# Sheet4.net
KiCad netlist of a schematic drawn in Altium Designer
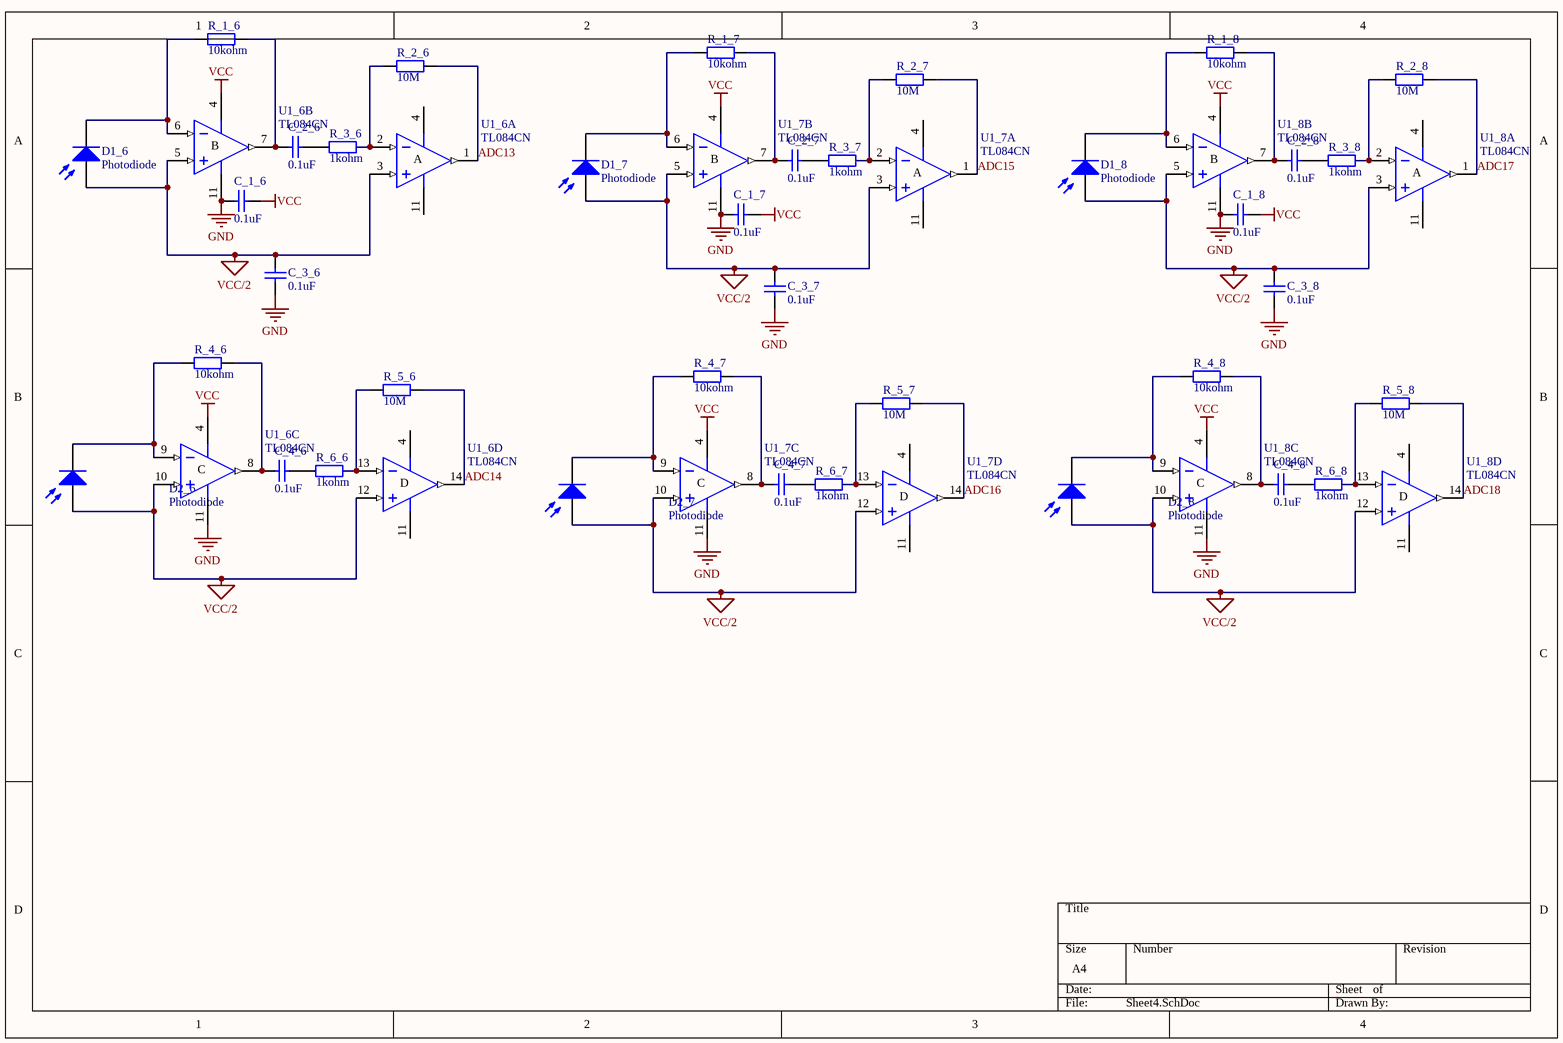
[diagram p0: Sheet4.SchDoc]

(export (version "E")
  (design (tool "Eeschema 10.0.6"))
  (components
    (comp (ref "C_1_6")
      (value "0.1uF")
      (footprint "cms805 - mini")
      (libsource (lib "lib_Robotronik") (part "Capa"))
    )
    (comp (ref "C_1_7")
      (value "0.1uF")
      (footprint "cms805 - mini")
      (libsource (lib "lib_Robotronik") (part "Capa"))
    )
    (comp (ref "C_1_8")
      (value "0.1uF")
      (footprint "cms805 - mini")
      (libsource (lib "lib_Robotronik") (part "Capa"))
    )
    (comp (ref "C_2_6")
      (value "0.1uF")
      (footprint "cms805 - mini")
      (libsource (lib "lib_Robotronik") (part "Capa"))
    )
    (comp (ref "C_2_7")
      (value "0.1uF")
      (footprint "cms805 - mini")
      (libsource (lib "lib_Robotronik") (part "Capa"))
    )
    (comp (ref "C_2_8")
      (value "0.1uF")
      (footprint "cms805 - mini")
      (libsource (lib "lib_Robotronik") (part "Capa"))
    )
    (comp (ref "C_3_6")
      (value "0.1uF")
      (footprint "cms805 - mini")
      (libsource (lib "lib_Robotronik") (part "Capa"))
    )
    (comp (ref "C_3_7")
      (value "0.1uF")
      (footprint "cms805 - mini")
      (libsource (lib "lib_Robotronik") (part "Capa"))
    )
    (comp (ref "C_3_8")
      (value "0.1uF")
      (footprint "cms805 - mini")
      (libsource (lib "lib_Robotronik") (part "Capa"))
    )
    (comp (ref "C_4_6")
      (value "0.1uF")
      (footprint "cms805 - mini")
      (libsource (lib "lib_Robotronik") (part "Capa"))
    )
    (comp (ref "C_4_7")
      (value "0.1uF")
      (footprint "cms805 - mini")
      (libsource (lib "lib_Robotronik") (part "Capa"))
    )
    (comp (ref "C_4_8")
      (value "0.1uF")
      (footprint "cms805 - mini")
      (libsource (lib "lib_Robotronik") (part "Capa"))
    )
    (comp (ref "D1_6")
      (value "Photodiode")
      (footprint "TEMD1000")
      (fields (field (name "PUBLISHER") "Altium Limited"))
      (libsource (lib "lib_Robotronik") (part "Photodiode"))
    )
    (comp (ref "D1_7")
      (value "Photodiode")
      (footprint "TEMD1000")
      (fields (field (name "PUBLISHER") "Altium Limited"))
      (libsource (lib "lib_Robotronik") (part "Photodiode"))
    )
    (comp (ref "D1_8")
      (value "Photodiode")
      (footprint "TEMD1000")
      (fields (field (name "PUBLISHER") "Altium Limited"))
      (libsource (lib "lib_Robotronik") (part "Photodiode"))
    )
    (comp (ref "D2_6")
      (value "Photodiode")
      (footprint "TEMD1000")
      (fields (field (name "PUBLISHER") "Altium Limited"))
      (libsource (lib "lib_Robotronik") (part "Photodiode"))
    )
    (comp (ref "D2_7")
      (value "Photodiode")
      (footprint "TEMD1000")
      (fields (field (name "PUBLISHER") "Altium Limited"))
      (libsource (lib "lib_Robotronik") (part "Photodiode"))
    )
    (comp (ref "D2_8")
      (value "Photodiode")
      (footprint "TEMD1000")
      (fields (field (name "PUBLISHER") "Altium Limited"))
      (libsource (lib "lib_Robotronik") (part "Photodiode"))
    )
    (comp (ref "R_1_6")
      (value "10kohm")
      (footprint "cms805 - mini")
      (libsource (lib "lib_Robotronik") (part "Resistance"))
    )
    (comp (ref "R_1_7")
      (value "10kohm")
      (footprint "cms805 - mini")
      (libsource (lib "lib_Robotronik") (part "Resistance"))
    )
    (comp (ref "R_1_8")
      (value "10kohm")
      (footprint "cms805 - mini")
      (libsource (lib "lib_Robotronik") (part "Resistance"))
    )
    (comp (ref "R_2_6")
      (value "10M")
      (footprint "cms805 - mini")
      (libsource (lib "lib_Robotronik") (part "Resistance"))
    )
    (comp (ref "R_2_7")
      (value "10M")
      (footprint "cms805 - mini")
      (libsource (lib "lib_Robotronik") (part "Resistance"))
    )
    (comp (ref "R_2_8")
      (value "10M")
      (footprint "cms805 - mini")
      (libsource (lib "lib_Robotronik") (part "Resistance"))
    )
    (comp (ref "R_3_6")
      (value "1kohm")
      (footprint "cms805 - mini")
      (libsource (lib "lib_Robotronik") (part "Resistance"))
    )
    (comp (ref "R_3_7")
      (value "1kohm")
      (footprint "cms805 - mini")
      (libsource (lib "lib_Robotronik") (part "Resistance"))
    )
    (comp (ref "R_3_8")
      (value "1kohm")
      (footprint "cms805 - mini")
      (libsource (lib "lib_Robotronik") (part "Resistance"))
    )
    (comp (ref "R_4_6")
      (value "10kohm")
      (footprint "cms805 - mini")
      (libsource (lib "lib_Robotronik") (part "Resistance"))
    )
    (comp (ref "R_4_7")
      (value "10kohm")
      (footprint "cms805 - mini")
      (libsource (lib "lib_Robotronik") (part "Resistance"))
    )
    (comp (ref "R_4_8")
      (value "10kohm")
      (footprint "cms805 - mini")
      (libsource (lib "lib_Robotronik") (part "Resistance"))
    )
    (comp (ref "R_5_6")
      (value "10M")
      (footprint "cms805 - mini")
      (libsource (lib "lib_Robotronik") (part "Resistance"))
    )
    (comp (ref "R_5_7")
      (value "10M")
      (footprint "cms805 - mini")
      (libsource (lib "lib_Robotronik") (part "Resistance"))
    )
    (comp (ref "R_5_8")
      (value "10M")
      (footprint "cms805 - mini")
      (libsource (lib "lib_Robotronik") (part "Resistance"))
    )
    (comp (ref "R_6_6")
      (value "1kohm")
      (footprint "cms805 - mini")
      (libsource (lib "lib_Robotronik") (part "Resistance"))
    )
    (comp (ref "R_6_7")
      (value "1kohm")
      (footprint "cms805 - mini")
      (libsource (lib "lib_Robotronik") (part "Resistance"))
    )
    (comp (ref "R_6_8")
      (value "1kohm")
      (footprint "cms805 - mini")
      (libsource (lib "lib_Robotronik") (part "Resistance"))
    )
    (comp (ref "U1_6")
      (value "TL084CN")
      (footprint "TSSOP14")
      (description "General-Purpose J-FET Quad Operational Amplifier")
      (fields (field (name "PUBLISHER") "Altium Limited"))
      (libsource (lib "lib_Robotronik") (part "TL084CN"))
    )
    (comp (ref "U1_7")
      (value "TL084CN")
      (footprint "TSSOP14")
      (description "General-Purpose J-FET Quad Operational Amplifier")
      (fields (field (name "PUBLISHER") "Altium Limited"))
      (libsource (lib "lib_Robotronik") (part "TL084CN"))
    )
    (comp (ref "U1_8")
      (value "TL084CN")
      (footprint "TSSOP14")
      (description "General-Purpose J-FET Quad Operational Amplifier")
      (fields (field (name "PUBLISHER") "Altium Limited"))
      (libsource (lib "lib_Robotronik") (part "TL084CN"))
    )
  )
  (nets
    (net (code "1") (name "/ADC13") (class "Default")
      (node (ref "R_2_6") (pin "2") (pinfunction "2_2") (pintype "passive"))
      (node (ref "U1_6") (pin "1") (pinfunction "OUT_1") (pintype "output"))
    )
    (net (code "2") (name "/ADC14") (class "Default")
      (node (ref "R_5_6") (pin "2") (pinfunction "2_2") (pintype "passive"))
      (node (ref "U1_6") (pin "14") (pinfunction "OUT_14") (pintype "output"))
    )
    (net (code "3") (name "/ADC15") (class "Default")
      (node (ref "R_2_7") (pin "2") (pinfunction "2_2") (pintype "passive"))
      (node (ref "U1_7") (pin "1") (pinfunction "OUT_1") (pintype "output"))
    )
    (net (code "4") (name "/ADC16") (class "Default")
      (node (ref "R_5_7") (pin "2") (pinfunction "2_2") (pintype "passive"))
      (node (ref "U1_7") (pin "14") (pinfunction "OUT_14") (pintype "output"))
    )
    (net (code "5") (name "/ADC17") (class "Default")
      (node (ref "R_2_8") (pin "2") (pinfunction "2_2") (pintype "passive"))
      (node (ref "U1_8") (pin "1") (pinfunction "OUT_1") (pintype "output"))
    )
    (net (code "6") (name "/ADC18") (class "Default")
      (node (ref "R_5_8") (pin "2") (pinfunction "2_2") (pintype "passive"))
      (node (ref "U1_8") (pin "14") (pinfunction "OUT_14") (pintype "output"))
    )
    (net (code "7") (name "GND") (class "Default")
      (node (ref "C_1_6") (pin "1") (pinfunction "1_1") (pintype "passive"))
      (node (ref "C_1_7") (pin "1") (pinfunction "1_1") (pintype "passive"))
      (node (ref "C_1_8") (pin "1") (pinfunction "1_1") (pintype "passive"))
      (node (ref "C_3_6") (pin "1") (pinfunction "1_1") (pintype "passive"))
      (node (ref "C_3_7") (pin "1") (pinfunction "1_1") (pintype "passive"))
      (node (ref "C_3_8") (pin "1") (pinfunction "1_1") (pintype "passive"))
      (node (ref "U1_6") (pin "11") (pinfunction "V-_11") (pintype "power_in"))
      (node (ref "U1_7") (pin "11") (pinfunction "V-_11") (pintype "power_in"))
      (node (ref "U1_8") (pin "11") (pinfunction "V-_11") (pintype "power_in"))
    )
    (net (code "8") (name "Net-(C_2_6-Pad1)") (class "Default")
      (node (ref "C_2_6") (pin "1") (pinfunction "1_1") (pintype "passive"))
      (node (ref "R_3_6") (pin "1") (pinfunction "1_1") (pintype "passive"))
    )
    (net (code "9") (name "Net-(C_2_7-Pad1)") (class "Default")
      (node (ref "C_2_7") (pin "1") (pinfunction "1_1") (pintype "passive"))
      (node (ref "R_3_7") (pin "1") (pinfunction "1_1") (pintype "passive"))
    )
    (net (code "10") (name "Net-(C_2_8-Pad1)") (class "Default")
      (node (ref "C_2_8") (pin "1") (pinfunction "1_1") (pintype "passive"))
      (node (ref "R_3_8") (pin "1") (pinfunction "1_1") (pintype "passive"))
    )
    (net (code "11") (name "Net-(C_4_6-Pad1)") (class "Default")
      (node (ref "C_4_6") (pin "1") (pinfunction "1_1") (pintype "passive"))
      (node (ref "R_6_6") (pin "1") (pinfunction "1_1") (pintype "passive"))
    )
    (net (code "12") (name "Net-(C_4_7-Pad1)") (class "Default")
      (node (ref "C_4_7") (pin "1") (pinfunction "1_1") (pintype "passive"))
      (node (ref "R_6_7") (pin "1") (pinfunction "1_1") (pintype "passive"))
    )
    (net (code "13") (name "Net-(C_4_8-Pad1)") (class "Default")
      (node (ref "C_4_8") (pin "1") (pinfunction "1_1") (pintype "passive"))
      (node (ref "R_6_8") (pin "1") (pinfunction "1_1") (pintype "passive"))
    )
    (net (code "14") (name "Net-(D1_6-K)") (class "Default")
      (node (ref "D1_6") (pin "2") (pinfunction "K_2") (pintype "passive"))
      (node (ref "R_1_6") (pin "1") (pinfunction "1_1") (pintype "passive"))
      (node (ref "U1_6") (pin "6") (pinfunction "IN-_6") (pintype "input"))
    )
    (net (code "15") (name "Net-(D1_7-K)") (class "Default")
      (node (ref "D1_7") (pin "2") (pinfunction "K_2") (pintype "passive"))
      (node (ref "R_1_7") (pin "1") (pinfunction "1_1") (pintype "passive"))
      (node (ref "U1_7") (pin "6") (pinfunction "IN-_6") (pintype "input"))
    )
    (net (code "16") (name "Net-(D1_8-K)") (class "Default")
      (node (ref "D1_8") (pin "2") (pinfunction "K_2") (pintype "passive"))
      (node (ref "R_1_8") (pin "1") (pinfunction "1_1") (pintype "passive"))
      (node (ref "U1_8") (pin "6") (pinfunction "IN-_6") (pintype "input"))
    )
    (net (code "17") (name "Net-(D2_6-K)") (class "Default")
      (node (ref "D2_6") (pin "2") (pinfunction "K_2") (pintype "passive"))
      (node (ref "R_4_6") (pin "1") (pinfunction "1_1") (pintype "passive"))
      (node (ref "U1_6") (pin "9") (pinfunction "IN-_9") (pintype "input"))
    )
    (net (code "18") (name "Net-(D2_7-K)") (class "Default")
      (node (ref "D2_7") (pin "2") (pinfunction "K_2") (pintype "passive"))
      (node (ref "R_4_7") (pin "1") (pinfunction "1_1") (pintype "passive"))
      (node (ref "U1_7") (pin "9") (pinfunction "IN-_9") (pintype "input"))
    )
    (net (code "19") (name "Net-(D2_8-K)") (class "Default")
      (node (ref "D2_8") (pin "2") (pinfunction "K_2") (pintype "passive"))
      (node (ref "R_4_8") (pin "1") (pinfunction "1_1") (pintype "passive"))
      (node (ref "U1_8") (pin "9") (pinfunction "IN-_9") (pintype "input"))
    )
    (net (code "20") (name "Net-(U1_6A-IN-)") (class "Default")
      (node (ref "R_2_6") (pin "1") (pinfunction "1_1") (pintype "passive"))
      (node (ref "R_3_6") (pin "2") (pinfunction "2_2") (pintype "passive"))
      (node (ref "U1_6") (pin "2") (pinfunction "IN-_2") (pintype "input"))
    )
    (net (code "21") (name "Net-(U1_6B-OUT)") (class "Default")
      (node (ref "C_2_6") (pin "2") (pinfunction "2_2") (pintype "passive"))
      (node (ref "R_1_6") (pin "2") (pinfunction "2_2") (pintype "passive"))
      (node (ref "U1_6") (pin "7") (pinfunction "OUT_7") (pintype "output"))
    )
    (net (code "22") (name "Net-(U1_6C-OUT)") (class "Default")
      (node (ref "C_4_6") (pin "2") (pinfunction "2_2") (pintype "passive"))
      (node (ref "R_4_6") (pin "2") (pinfunction "2_2") (pintype "passive"))
      (node (ref "U1_6") (pin "8") (pinfunction "OUT_8") (pintype "output"))
    )
    (net (code "23") (name "Net-(U1_6D-IN-)") (class "Default")
      (node (ref "R_5_6") (pin "1") (pinfunction "1_1") (pintype "passive"))
      (node (ref "R_6_6") (pin "2") (pinfunction "2_2") (pintype "passive"))
      (node (ref "U1_6") (pin "13") (pinfunction "IN-_13") (pintype "input"))
    )
    (net (code "24") (name "Net-(U1_7A-IN-)") (class "Default")
      (node (ref "R_2_7") (pin "1") (pinfunction "1_1") (pintype "passive"))
      (node (ref "R_3_7") (pin "2") (pinfunction "2_2") (pintype "passive"))
      (node (ref "U1_7") (pin "2") (pinfunction "IN-_2") (pintype "input"))
    )
    (net (code "25") (name "Net-(U1_7B-OUT)") (class "Default")
      (node (ref "C_2_7") (pin "2") (pinfunction "2_2") (pintype "passive"))
      (node (ref "R_1_7") (pin "2") (pinfunction "2_2") (pintype "passive"))
      (node (ref "U1_7") (pin "7") (pinfunction "OUT_7") (pintype "output"))
    )
    (net (code "26") (name "Net-(U1_7C-OUT)") (class "Default")
      (node (ref "C_4_7") (pin "2") (pinfunction "2_2") (pintype "passive"))
      (node (ref "R_4_7") (pin "2") (pinfunction "2_2") (pintype "passive"))
      (node (ref "U1_7") (pin "8") (pinfunction "OUT_8") (pintype "output"))
    )
    (net (code "27") (name "Net-(U1_7D-IN-)") (class "Default")
      (node (ref "R_5_7") (pin "1") (pinfunction "1_1") (pintype "passive"))
      (node (ref "R_6_7") (pin "2") (pinfunction "2_2") (pintype "passive"))
      (node (ref "U1_7") (pin "13") (pinfunction "IN-_13") (pintype "input"))
    )
    (net (code "28") (name "Net-(U1_8A-IN-)") (class "Default")
      (node (ref "R_2_8") (pin "1") (pinfunction "1_1") (pintype "passive"))
      (node (ref "R_3_8") (pin "2") (pinfunction "2_2") (pintype "passive"))
      (node (ref "U1_8") (pin "2") (pinfunction "IN-_2") (pintype "input"))
    )
    (net (code "29") (name "Net-(U1_8B-OUT)") (class "Default")
      (node (ref "C_2_8") (pin "2") (pinfunction "2_2") (pintype "passive"))
      (node (ref "R_1_8") (pin "2") (pinfunction "2_2") (pintype "passive"))
      (node (ref "U1_8") (pin "7") (pinfunction "OUT_7") (pintype "output"))
    )
    (net (code "30") (name "Net-(U1_8C-OUT)") (class "Default")
      (node (ref "C_4_8") (pin "2") (pinfunction "2_2") (pintype "passive"))
      (node (ref "R_4_8") (pin "2") (pinfunction "2_2") (pintype "passive"))
      (node (ref "U1_8") (pin "8") (pinfunction "OUT_8") (pintype "output"))
    )
    (net (code "31") (name "Net-(U1_8D-IN-)") (class "Default")
      (node (ref "R_5_8") (pin "1") (pinfunction "1_1") (pintype "passive"))
      (node (ref "R_6_8") (pin "2") (pinfunction "2_2") (pintype "passive"))
      (node (ref "U1_8") (pin "13") (pinfunction "IN-_13") (pintype "input"))
    )
    (net (code "32") (name "VCC") (class "Default")
      (node (ref "C_1_6") (pin "2") (pinfunction "2_2") (pintype "passive"))
      (node (ref "C_1_7") (pin "2") (pinfunction "2_2") (pintype "passive"))
      (node (ref "C_1_8") (pin "2") (pinfunction "2_2") (pintype "passive"))
      (node (ref "U1_6") (pin "4") (pinfunction "V+_4") (pintype "power_in"))
      (node (ref "U1_7") (pin "4") (pinfunction "V+_4") (pintype "power_in"))
      (node (ref "U1_8") (pin "4") (pinfunction "V+_4") (pintype "power_in"))
    )
    (net (code "33") (name "VCC{slash}2") (class "Default")
      (node (ref "C_3_6") (pin "2") (pinfunction "2_2") (pintype "passive"))
      (node (ref "C_3_7") (pin "2") (pinfunction "2_2") (pintype "passive"))
      (node (ref "C_3_8") (pin "2") (pinfunction "2_2") (pintype "passive"))
      (node (ref "D1_6") (pin "1") (pinfunction "A_1") (pintype "passive"))
      (node (ref "D1_7") (pin "1") (pinfunction "A_1") (pintype "passive"))
      (node (ref "D1_8") (pin "1") (pinfunction "A_1") (pintype "passive"))
      (node (ref "D2_6") (pin "1") (pinfunction "A_1") (pintype "passive"))
      (node (ref "D2_7") (pin "1") (pinfunction "A_1") (pintype "passive"))
      (node (ref "D2_8") (pin "1") (pinfunction "A_1") (pintype "passive"))
      (node (ref "U1_6") (pin "10") (pinfunction "IN+_10") (pintype "input"))
      (node (ref "U1_6") (pin "12") (pinfunction "IN+_12") (pintype "input"))
      (node (ref "U1_6") (pin "3") (pinfunction "IN+_3") (pintype "input"))
      (node (ref "U1_6") (pin "5") (pinfunction "IN+_5") (pintype "input"))
      (node (ref "U1_7") (pin "10") (pinfunction "IN+_10") (pintype "input"))
      (node (ref "U1_7") (pin "12") (pinfunction "IN+_12") (pintype "input"))
      (node (ref "U1_7") (pin "3") (pinfunction "IN+_3") (pintype "input"))
      (node (ref "U1_7") (pin "5") (pinfunction "IN+_5") (pintype "input"))
      (node (ref "U1_8") (pin "10") (pinfunction "IN+_10") (pintype "input"))
      (node (ref "U1_8") (pin "12") (pinfunction "IN+_12") (pintype "input"))
      (node (ref "U1_8") (pin "3") (pinfunction "IN+_3") (pintype "input"))
      (node (ref "U1_8") (pin "5") (pinfunction "IN+_5") (pintype "input"))
    )
    (net (code "34") (name "unconnected-(U1_6A-V+-Pad4)") (class "Default")
      (node (ref "U1_6") (pin "4") (pinfunction "V+_4") (pintype "power_in"))
    )
    (net (code "35") (name "unconnected-(U1_6A-V--Pad11)") (class "Default")
      (node (ref "U1_6") (pin "11") (pinfunction "V-_11") (pintype "power_in"))
    )
    (net (code "36") (name "unconnected-(U1_6D-V+-Pad4)") (class "Default")
      (node (ref "U1_6") (pin "4") (pinfunction "V+_4") (pintype "power_in"))
    )
    (net (code "37") (name "unconnected-(U1_6D-V--Pad11)") (class "Default")
      (node (ref "U1_6") (pin "11") (pinfunction "V-_11") (pintype "power_in"))
    )
    (net (code "38") (name "unconnected-(U1_7A-V+-Pad4)") (class "Default")
      (node (ref "U1_7") (pin "4") (pinfunction "V+_4") (pintype "power_in"))
    )
    (net (code "39") (name "unconnected-(U1_7A-V--Pad11)") (class "Default")
      (node (ref "U1_7") (pin "11") (pinfunction "V-_11") (pintype "power_in"))
    )
    (net (code "40") (name "unconnected-(U1_7D-V+-Pad4)") (class "Default")
      (node (ref "U1_7") (pin "4") (pinfunction "V+_4") (pintype "power_in"))
    )
    (net (code "41") (name "unconnected-(U1_7D-V--Pad11)") (class "Default")
      (node (ref "U1_7") (pin "11") (pinfunction "V-_11") (pintype "power_in"))
    )
    (net (code "42") (name "unconnected-(U1_8A-V+-Pad4)") (class "Default")
      (node (ref "U1_8") (pin "4") (pinfunction "V+_4") (pintype "power_in"))
    )
    (net (code "43") (name "unconnected-(U1_8A-V--Pad11)") (class "Default")
      (node (ref "U1_8") (pin "11") (pinfunction "V-_11") (pintype "power_in"))
    )
    (net (code "44") (name "unconnected-(U1_8D-V+-Pad4)") (class "Default")
      (node (ref "U1_8") (pin "4") (pinfunction "V+_4") (pintype "power_in"))
    )
    (net (code "45") (name "unconnected-(U1_8D-V--Pad11)") (class "Default")
      (node (ref "U1_8") (pin "11") (pinfunction "V-_11") (pintype "power_in"))
    )
  )
)
